# LED_GROUP.net
KiCad netlist of a schematic drawn in Altium Designer
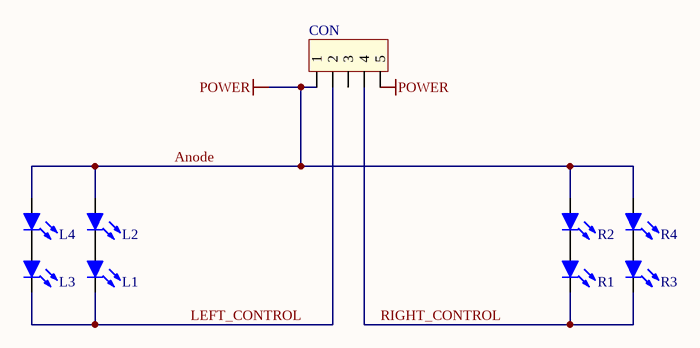
[diagram p0: LED_GROUP.SchDoc]

(export (version "E")
  (design (tool "Eeschema 10.0.6"))
  (components
    (comp (ref "CON")
      (value "Giắc XH 5P 2.54 chống cắm ngược chiều")
      (footprint "swatpcblib:XH_5P_254")
      (description "Connector 5")
      (libsource (lib "heromap") (part "Con5"))
    )
    (comp (ref "L1")
      (value "Mạch đèn LED bên trái")
      (footprint "LED_GROUP:LED OSRAM CIRCUIT")
      (libsource (lib "swatpcblib") (part "Led"))
    )
    (comp (ref "L2")
      (value "Mạch đèn LED bên trái")
      (footprint "LED_GROUP:LED OSRAM CIRCUIT")
      (libsource (lib "swatpcblib") (part "Led"))
    )
    (comp (ref "L3")
      (value "Mạch đèn LED bên trái")
      (footprint "LED_GROUP:LED OSRAM CIRCUIT")
      (libsource (lib "swatpcblib") (part "Led"))
    )
    (comp (ref "L4")
      (value "Mạch đèn LED bên trái")
      (footprint "LED_GROUP:LED OSRAM CIRCUIT")
      (libsource (lib "swatpcblib") (part "Led"))
    )
    (comp (ref "R1")
      (value "Mạch đèn LED bên phải")
      (footprint "LED_GROUP:LED OSRAM CIRCUIT")
      (libsource (lib "swatpcblib") (part "Led"))
    )
    (comp (ref "R2")
      (value "Mạch đèn LED bên phải")
      (footprint "LED_GROUP:LED OSRAM CIRCUIT")
      (libsource (lib "swatpcblib") (part "Led"))
    )
    (comp (ref "R3")
      (value "Mạch đèn LED bên phải")
      (footprint "LED_GROUP:LED OSRAM CIRCUIT")
      (libsource (lib "swatpcblib") (part "Led"))
    )
    (comp (ref "R4")
      (value "Mạch đèn LED bên phải")
      (footprint "LED_GROUP:LED OSRAM CIRCUIT")
      (libsource (lib "swatpcblib") (part "Led"))
    )
  )
  (nets
    (net (code "1") (name "/LEFT_CONTROL") (class "Default")
      (node (ref "CON") (pin "2") (pinfunction "2_2") (pintype "passive"))
      (node (ref "L1") (pin "K") (pinfunction "K_K") (pintype "passive"))
      (node (ref "L3") (pin "K") (pinfunction "K_K") (pintype "passive"))
    )
    (net (code "2") (name "/RIGHT_CONTROL") (class "Default")
      (node (ref "CON") (pin "4") (pinfunction "4_4") (pintype "passive"))
      (node (ref "R1") (pin "K") (pinfunction "K_K") (pintype "passive"))
      (node (ref "R3") (pin "K") (pinfunction "K_K") (pintype "passive"))
    )
    (net (code "3") (name "Net-(L1-PadA)") (class "Default")
      (node (ref "L1") (pin "A") (pinfunction "A_A") (pintype "passive"))
      (node (ref "L2") (pin "K") (pinfunction "K_K") (pintype "passive"))
    )
    (net (code "4") (name "Net-(L3-PadA)") (class "Default")
      (node (ref "L3") (pin "A") (pinfunction "A_A") (pintype "passive"))
      (node (ref "L4") (pin "K") (pinfunction "K_K") (pintype "passive"))
    )
    (net (code "5") (name "Net-(R1-PadA)") (class "Default")
      (node (ref "R1") (pin "A") (pinfunction "A_A") (pintype "passive"))
      (node (ref "R2") (pin "K") (pinfunction "K_K") (pintype "passive"))
    )
    (net (code "6") (name "Net-(R3-PadA)") (class "Default")
      (node (ref "R3") (pin "A") (pinfunction "A_A") (pintype "passive"))
      (node (ref "R4") (pin "K") (pinfunction "K_K") (pintype "passive"))
    )
    (net (code "7") (name "POWER") (class "Default")
      (node (ref "CON") (pin "1") (pinfunction "1_1") (pintype "passive"))
      (node (ref "CON") (pin "5") (pinfunction "5_5") (pintype "passive"))
      (node (ref "L2") (pin "A") (pinfunction "A_A") (pintype "passive"))
      (node (ref "L4") (pin "A") (pinfunction "A_A") (pintype "passive"))
      (node (ref "R2") (pin "A") (pinfunction "A_A") (pintype "passive"))
      (node (ref "R4") (pin "A") (pinfunction "A_A") (pintype "passive"))
    )
    (net (code "8") (name "unconnected-(CON-Pad3)") (class "Default")
      (node (ref "CON") (pin "3") (pinfunction "3_3") (pintype "passive"))
    )
  )
)
